# InterfaceUtil.net
KiCad netlist of a schematic drawn in Altium Designer
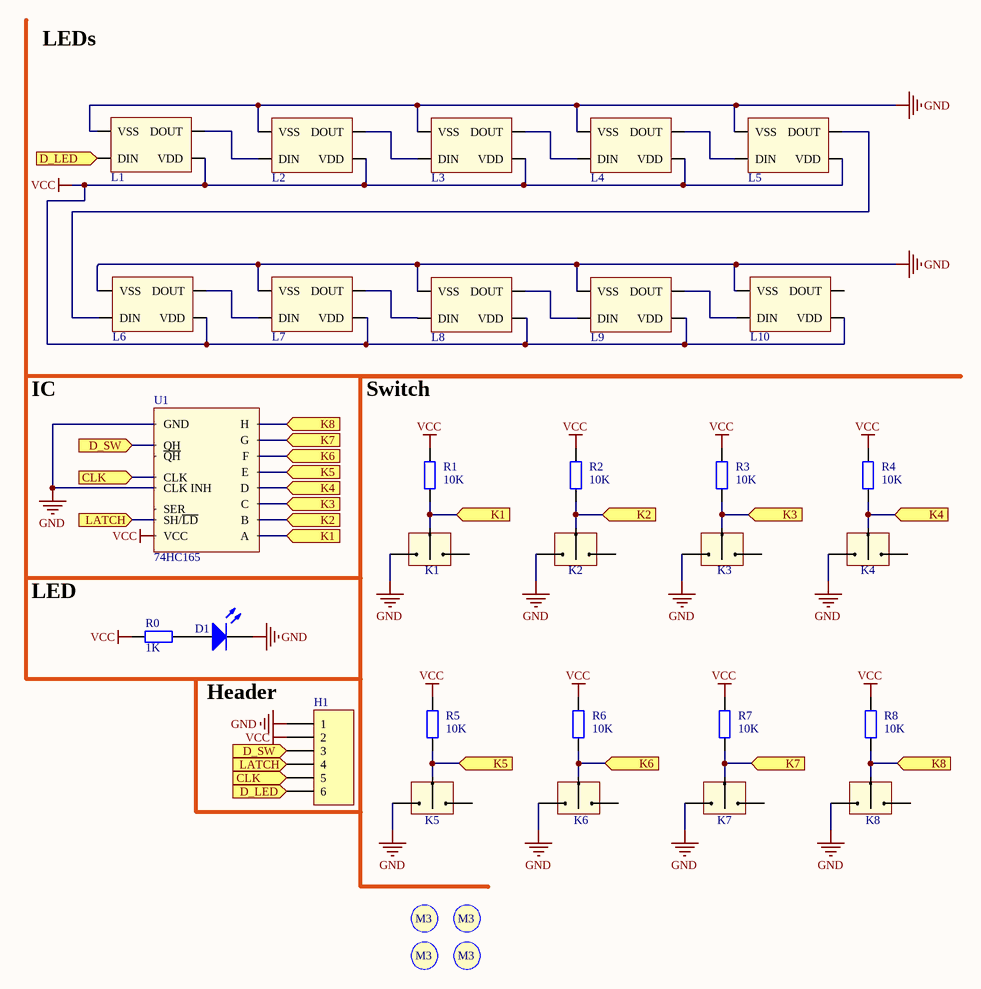
[diagram p0: InterfaceUtil.SchDoc]

(export (version "E")
  (design (tool "Eeschema 10.0.6"))
  (components
    (comp (ref "D1")
      (value "LED2")
      (footprint "3.2X1.6X1.1")
      (description "Typical RED, GREEN, YELLOW, AMBER GaAs LED")
      (fields (field (name "PUBLISHER") "Altium Limited"))
      (libsource (lib "Miscellaneous Devices") (part "LED2"))
    )
    (comp (ref "H1")
      (value "Header 6")
      (footprint "Robot_2019:MOLEX SPOX 6X1H")
      (description "Header, 6-Pin")
      (fields (field (name "PUBLISHER") "Altium Limited"))
      (libsource (lib "Miscellaneous Connectors") (part "Header 6"))
    )
    (comp (ref "K1")
      (value "Switch")
      (footprint "robot:SWITCH")
      (description "3 pos switch, 09.03290.01")
      (libsource (lib "Robot_2019") (part "Switch"))
    )
    (comp (ref "K2")
      (value "Switch")
      (footprint "robot:SWITCH")
      (description "3 pos switch, 09.03290.01")
      (libsource (lib "Robot_2019") (part "Switch"))
    )
    (comp (ref "K3")
      (value "Switch")
      (footprint "robot:SWITCH")
      (description "3 pos switch, 09.03290.01")
      (libsource (lib "Robot_2019") (part "Switch"))
    )
    (comp (ref "K4")
      (value "Switch")
      (footprint "robot:SWITCH")
      (description "3 pos switch, 09.03290.01")
      (libsource (lib "Robot_2019") (part "Switch"))
    )
    (comp (ref "K5")
      (value "Switch")
      (footprint "Robot_2019:SWITCH")
      (description "3 pos switch, 09.03290.01")
      (libsource (lib "Robot_2019") (part "Switch"))
    )
    (comp (ref "K6")
      (value "Switch")
      (footprint "robot:SWITCH")
      (description "3 pos switch, 09.03290.01")
      (libsource (lib "Robot_2019") (part "Switch"))
    )
    (comp (ref "K7")
      (value "Switch")
      (footprint "robot:SWITCH")
      (description "3 pos switch, 09.03290.01")
      (libsource (lib "Robot_2019") (part "Switch"))
    )
    (comp (ref "K8")
      (value "Switch")
      (footprint "robot:SWITCH")
      (description "3 pos switch, 09.03290.01")
      (libsource (lib "Robot_2019") (part "Switch"))
    )
    (comp (ref "L1")
      (value "NeoPixel")
      (footprint "robot:Neopixel")
      (libsource (lib "robot") (part "NeoPixel"))
    )
    (comp (ref "L2")
      (value "NeoPixel")
      (footprint "robot:Neopixel")
      (libsource (lib "robot") (part "NeoPixel"))
    )
    (comp (ref "L3")
      (value "NeoPixel")
      (footprint "robot:Neopixel")
      (libsource (lib "robot") (part "NeoPixel"))
    )
    (comp (ref "L4")
      (value "NeoPixel")
      (footprint "robot:Neopixel")
      (libsource (lib "robot") (part "NeoPixel"))
    )
    (comp (ref "L5")
      (value "NeoPixel")
      (footprint "robot:Neopixel")
      (libsource (lib "robot") (part "NeoPixel"))
    )
    (comp (ref "L6")
      (value "NeoPixel")
      (footprint "robot:Neopixel")
      (libsource (lib "robot") (part "NeoPixel"))
    )
    (comp (ref "L7")
      (value "NeoPixel")
      (footprint "robot:Neopixel")
      (libsource (lib "robot") (part "NeoPixel"))
    )
    (comp (ref "L8")
      (value "NeoPixel")
      (footprint "robot:Neopixel")
      (libsource (lib "robot") (part "NeoPixel"))
    )
    (comp (ref "L9")
      (value "NeoPixel")
      (footprint "robot:Neopixel")
      (libsource (lib "robot") (part "NeoPixel"))
    )
    (comp (ref "L10")
      (value "NeoPixel")
      (footprint "robot:Neopixel")
      (libsource (lib "robot") (part "NeoPixel"))
    )
    (comp (ref "R0")
      (value "1K")
      (footprint "3.2X1.6X1.1")
      (description "Resistor")
      (fields (field (name "Comment") "Res2") (field (name "PUBLISHER") "Altium Limited"))
      (libsource (lib "") (part "Res2_1"))
    )
    (comp (ref "R1")
      (value "10K")
      (footprint "3.2X1.6X1.1")
      (description "Resistor")
      (fields (field (name "Comment") "Res2") (field (name "PUBLISHER") "Altium Limited"))
      (libsource (lib "Miscellaneous Devices") (part "Res2"))
    )
    (comp (ref "R2")
      (value "10K")
      (footprint "3.2X1.6X1.1")
      (description "Resistor")
      (fields (field (name "Comment") "Res2") (field (name "PUBLISHER") "Altium Limited"))
      (libsource (lib "Miscellaneous Devices") (part "Res2"))
    )
    (comp (ref "R3")
      (value "10K")
      (footprint "3.2X1.6X1.1")
      (description "Resistor")
      (fields (field (name "Comment") "Res2") (field (name "PUBLISHER") "Altium Limited"))
      (libsource (lib "Miscellaneous Devices") (part "Res2"))
    )
    (comp (ref "R4")
      (value "10K")
      (footprint "3.2X1.6X1.1")
      (description "Resistor")
      (fields (field (name "Comment") "Res2") (field (name "PUBLISHER") "Altium Limited"))
      (libsource (lib "Miscellaneous Devices") (part "Res2"))
    )
    (comp (ref "R5")
      (value "10K")
      (footprint "3.2X1.6X1.1")
      (description "Resistor")
      (fields (field (name "Comment") "Res2") (field (name "PUBLISHER") "Altium Limited"))
      (libsource (lib "Miscellaneous Devices") (part "Res2"))
    )
    (comp (ref "R6")
      (value "10K")
      (footprint "3.2X1.6X1.1")
      (description "Resistor")
      (fields (field (name "Comment") "Res2") (field (name "PUBLISHER") "Altium Limited"))
      (libsource (lib "Miscellaneous Devices") (part "Res2"))
    )
    (comp (ref "R7")
      (value "10K")
      (footprint "3.2X1.6X1.1")
      (description "Resistor")
      (fields (field (name "Comment") "Res2") (field (name "PUBLISHER") "Altium Limited"))
      (libsource (lib "Miscellaneous Devices") (part "Res2"))
    )
    (comp (ref "R8")
      (value "10K")
      (footprint "3.2X1.6X1.1")
      (description "Resistor")
      (fields (field (name "Comment") "Res2") (field (name "PUBLISHER") "Altium Limited"))
      (libsource (lib "Miscellaneous Devices") (part "Res2"))
    )
    (comp (ref "S1")
      (value "Screw M3")
      (footprint "Robot_2019:Screw M3")
      (libsource (lib "Robot_2019") (part "Screw M3"))
    )
    (comp (ref "S2")
      (value "Screw M3")
      (footprint "Robot_2019:Screw M3")
      (libsource (lib "Robot_2019") (part "Screw M3"))
    )
    (comp (ref "S3")
      (value "Screw M3")
      (footprint "Robot_2019:Screw M3")
      (libsource (lib "Robot_2019") (part "Screw M3"))
    )
    (comp (ref "S4")
      (value "Screw M3")
      (footprint "Robot_2019:Screw M3")
      (libsource (lib "Robot_2019") (part "Screw M3"))
    )
    (comp (ref "U1")
      (value "74HC165")
      (footprint "Robot_2019:16 pins SOIC, TI")
      (description "8 bits Shift Register")
      (libsource (lib "Robot_2019") (part "SN74HC165"))
    )
  )
  (nets
    (net (code "1") (name "/CLK") (class "Default")
      (node (ref "H1") (pin "5") (pinfunction "5_5") (pintype "passive"))
      (node (ref "U1") (pin "2") (pinfunction "CLK_2") (pintype "passive"))
    )
    (net (code "2") (name "/D_LED") (class "Default")
      (node (ref "H1") (pin "6") (pinfunction "6_6") (pintype "passive"))
      (node (ref "L1") (pin "2") (pinfunction "DIN_2") (pintype "passive"))
    )
    (net (code "3") (name "/D_SW") (class "Default")
      (node (ref "H1") (pin "3") (pinfunction "3_3") (pintype "passive"))
      (node (ref "U1") (pin "9") (pinfunction "QH_9") (pintype "passive"))
    )
    (net (code "4") (name "/K1") (class "Default")
      (node (ref "K1") (pin "1") (pinfunction "M_1") (pintype "passive"))
      (node (ref "R1") (pin "1") (pinfunction "1_1") (pintype "passive"))
      (node (ref "U1") (pin "11") (pinfunction "A_11") (pintype "passive"))
    )
    (net (code "5") (name "/K2") (class "Default")
      (node (ref "K2") (pin "1") (pinfunction "M_1") (pintype "passive"))
      (node (ref "R2") (pin "1") (pinfunction "1_1") (pintype "passive"))
      (node (ref "U1") (pin "12") (pinfunction "B_12") (pintype "passive"))
    )
    (net (code "6") (name "/K3") (class "Default")
      (node (ref "K3") (pin "1") (pinfunction "M_1") (pintype "passive"))
      (node (ref "R3") (pin "1") (pinfunction "1_1") (pintype "passive"))
      (node (ref "U1") (pin "13") (pinfunction "C_13") (pintype "passive"))
    )
    (net (code "7") (name "/K4") (class "Default")
      (node (ref "K4") (pin "1") (pinfunction "M_1") (pintype "passive"))
      (node (ref "R4") (pin "1") (pinfunction "1_1") (pintype "passive"))
      (node (ref "U1") (pin "14") (pinfunction "D_14") (pintype "passive"))
    )
    (net (code "8") (name "/K5") (class "Default")
      (node (ref "K5") (pin "1") (pinfunction "M_1") (pintype "passive"))
      (node (ref "R5") (pin "1") (pinfunction "1_1") (pintype "passive"))
      (node (ref "U1") (pin "3") (pinfunction "E_3") (pintype "passive"))
    )
    (net (code "9") (name "/K6") (class "Default")
      (node (ref "K6") (pin "1") (pinfunction "M_1") (pintype "passive"))
      (node (ref "R6") (pin "1") (pinfunction "1_1") (pintype "passive"))
      (node (ref "U1") (pin "4") (pinfunction "F_4") (pintype "passive"))
    )
    (net (code "10") (name "/K7") (class "Default")
      (node (ref "K7") (pin "1") (pinfunction "M_1") (pintype "passive"))
      (node (ref "R7") (pin "1") (pinfunction "1_1") (pintype "passive"))
      (node (ref "U1") (pin "5") (pinfunction "G_5") (pintype "passive"))
    )
    (net (code "11") (name "/K8") (class "Default")
      (node (ref "K8") (pin "1") (pinfunction "M_1") (pintype "passive"))
      (node (ref "R8") (pin "1") (pinfunction "1_1") (pintype "passive"))
      (node (ref "U1") (pin "6") (pinfunction "H_6") (pintype "passive"))
    )
    (net (code "12") (name "/LATCH") (class "Default")
      (node (ref "H1") (pin "4") (pinfunction "4_4") (pintype "passive"))
      (node (ref "U1") (pin "1") (pinfunction "SH/~{LD}_1") (pintype "passive"))
    )
    (net (code "13") (name "GND") (class "Default")
      (node (ref "D1") (pin "2") (pinfunction "K_2") (pintype "passive"))
      (node (ref "H1") (pin "1") (pinfunction "1_1") (pintype "passive"))
      (node (ref "K1") (pin "0") (pinfunction "L_0") (pintype "passive"))
      (node (ref "K2") (pin "0") (pinfunction "L_0") (pintype "passive"))
      (node (ref "K3") (pin "0") (pinfunction "L_0") (pintype "passive"))
      (node (ref "K4") (pin "0") (pinfunction "L_0") (pintype "passive"))
      (node (ref "K5") (pin "0") (pinfunction "L_0") (pintype "passive"))
      (node (ref "K6") (pin "0") (pinfunction "L_0") (pintype "passive"))
      (node (ref "K7") (pin "0") (pinfunction "L_0") (pintype "passive"))
      (node (ref "K8") (pin "0") (pinfunction "L_0") (pintype "passive"))
      (node (ref "L1") (pin "1") (pinfunction "VSS_1") (pintype "passive"))
      (node (ref "L10") (pin "1") (pinfunction "VSS_1") (pintype "passive"))
      (node (ref "L2") (pin "1") (pinfunction "VSS_1") (pintype "passive"))
      (node (ref "L3") (pin "1") (pinfunction "VSS_1") (pintype "passive"))
      (node (ref "L4") (pin "1") (pinfunction "VSS_1") (pintype "passive"))
      (node (ref "L5") (pin "1") (pinfunction "VSS_1") (pintype "passive"))
      (node (ref "L6") (pin "1") (pinfunction "VSS_1") (pintype "passive"))
      (node (ref "L7") (pin "1") (pinfunction "VSS_1") (pintype "passive"))
      (node (ref "L8") (pin "1") (pinfunction "VSS_1") (pintype "passive"))
      (node (ref "L9") (pin "1") (pinfunction "VSS_1") (pintype "passive"))
      (node (ref "U1") (pin "15") (pinfunction "CLK_INH_15") (pintype "passive"))
      (node (ref "U1") (pin "8") (pinfunction "GND_8") (pintype "passive"))
    )
    (net (code "14") (name "Net-(D1-A)") (class "Default")
      (node (ref "D1") (pin "1") (pinfunction "A_1") (pintype "passive"))
      (node (ref "R0") (pin "2") (pinfunction "2_2") (pintype "passive"))
    )
    (net (code "15") (name "Net-(L1-DOUT)") (class "Default")
      (node (ref "L1") (pin "4") (pinfunction "DOUT_4") (pintype "passive"))
      (node (ref "L2") (pin "2") (pinfunction "DIN_2") (pintype "passive"))
    )
    (net (code "16") (name "Net-(L2-DOUT)") (class "Default")
      (node (ref "L2") (pin "4") (pinfunction "DOUT_4") (pintype "passive"))
      (node (ref "L3") (pin "2") (pinfunction "DIN_2") (pintype "passive"))
    )
    (net (code "17") (name "Net-(L3-DOUT)") (class "Default")
      (node (ref "L3") (pin "4") (pinfunction "DOUT_4") (pintype "passive"))
      (node (ref "L4") (pin "2") (pinfunction "DIN_2") (pintype "passive"))
    )
    (net (code "18") (name "Net-(L4-DOUT)") (class "Default")
      (node (ref "L4") (pin "4") (pinfunction "DOUT_4") (pintype "passive"))
      (node (ref "L5") (pin "2") (pinfunction "DIN_2") (pintype "passive"))
    )
    (net (code "19") (name "Net-(L5-DOUT)") (class "Default")
      (node (ref "L5") (pin "4") (pinfunction "DOUT_4") (pintype "passive"))
      (node (ref "L6") (pin "2") (pinfunction "DIN_2") (pintype "passive"))
    )
    (net (code "20") (name "Net-(L6-DOUT)") (class "Default")
      (node (ref "L6") (pin "4") (pinfunction "DOUT_4") (pintype "passive"))
      (node (ref "L7") (pin "2") (pinfunction "DIN_2") (pintype "passive"))
    )
    (net (code "21") (name "Net-(L7-DOUT)") (class "Default")
      (node (ref "L7") (pin "4") (pinfunction "DOUT_4") (pintype "passive"))
      (node (ref "L8") (pin "2") (pinfunction "DIN_2") (pintype "passive"))
    )
    (net (code "22") (name "Net-(L8-DOUT)") (class "Default")
      (node (ref "L8") (pin "4") (pinfunction "DOUT_4") (pintype "passive"))
      (node (ref "L9") (pin "2") (pinfunction "DIN_2") (pintype "passive"))
    )
    (net (code "23") (name "Net-(L10-DIN)") (class "Default")
      (node (ref "L10") (pin "2") (pinfunction "DIN_2") (pintype "passive"))
      (node (ref "L9") (pin "4") (pinfunction "DOUT_4") (pintype "passive"))
    )
    (net (code "24") (name "VCC") (class "Default")
      (node (ref "H1") (pin "2") (pinfunction "2_2") (pintype "passive"))
      (node (ref "L1") (pin "3") (pinfunction "VDD_3") (pintype "passive"))
      (node (ref "L10") (pin "3") (pinfunction "VDD_3") (pintype "passive"))
      (node (ref "L2") (pin "3") (pinfunction "VDD_3") (pintype "passive"))
      (node (ref "L3") (pin "3") (pinfunction "VDD_3") (pintype "passive"))
      (node (ref "L4") (pin "3") (pinfunction "VDD_3") (pintype "passive"))
      (node (ref "L5") (pin "3") (pinfunction "VDD_3") (pintype "passive"))
      (node (ref "L6") (pin "3") (pinfunction "VDD_3") (pintype "passive"))
      (node (ref "L7") (pin "3") (pinfunction "VDD_3") (pintype "passive"))
      (node (ref "L8") (pin "3") (pinfunction "VDD_3") (pintype "passive"))
      (node (ref "L9") (pin "3") (pinfunction "VDD_3") (pintype "passive"))
      (node (ref "R0") (pin "1") (pinfunction "1_1") (pintype "passive"))
      (node (ref "R1") (pin "2") (pinfunction "2_2") (pintype "passive"))
      (node (ref "R2") (pin "2") (pinfunction "2_2") (pintype "passive"))
      (node (ref "R3") (pin "2") (pinfunction "2_2") (pintype "passive"))
      (node (ref "R4") (pin "2") (pinfunction "2_2") (pintype "passive"))
      (node (ref "R5") (pin "2") (pinfunction "2_2") (pintype "passive"))
      (node (ref "R6") (pin "2") (pinfunction "2_2") (pintype "passive"))
      (node (ref "R7") (pin "2") (pinfunction "2_2") (pintype "passive"))
      (node (ref "R8") (pin "2") (pinfunction "2_2") (pintype "passive"))
      (node (ref "U1") (pin "16") (pinfunction "VCC_16") (pintype "passive"))
    )
    (net (code "25") (name "unconnected-(K1-R-Pad2)") (class "Default")
      (node (ref "K1") (pin "2") (pinfunction "R_2") (pintype "passive"))
    )
    (net (code "26") (name "unconnected-(K2-R-Pad2)") (class "Default")
      (node (ref "K2") (pin "2") (pinfunction "R_2") (pintype "passive"))
    )
    (net (code "27") (name "unconnected-(K3-R-Pad2)") (class "Default")
      (node (ref "K3") (pin "2") (pinfunction "R_2") (pintype "passive"))
    )
    (net (code "28") (name "unconnected-(K4-R-Pad2)") (class "Default")
      (node (ref "K4") (pin "2") (pinfunction "R_2") (pintype "passive"))
    )
    (net (code "29") (name "unconnected-(K5-R-Pad2)") (class "Default")
      (node (ref "K5") (pin "2") (pinfunction "R_2") (pintype "passive"))
    )
    (net (code "30") (name "unconnected-(K6-R-Pad2)") (class "Default")
      (node (ref "K6") (pin "2") (pinfunction "R_2") (pintype "passive"))
    )
    (net (code "31") (name "unconnected-(K7-R-Pad2)") (class "Default")
      (node (ref "K7") (pin "2") (pinfunction "R_2") (pintype "passive"))
    )
    (net (code "32") (name "unconnected-(K8-R-Pad2)") (class "Default")
      (node (ref "K8") (pin "2") (pinfunction "R_2") (pintype "passive"))
    )
    (net (code "33") (name "unconnected-(L10-DOUT-Pad4)") (class "Default")
      (node (ref "L10") (pin "4") (pinfunction "DOUT_4") (pintype "passive"))
    )
    (net (code "34") (name "unconnected-(U1-SER-Pad10)") (class "Default")
      (node (ref "U1") (pin "10") (pinfunction "SER_10") (pintype "passive"))
    )
    (net (code "35") (name "unconnected-(U1-~{QH}-Pad7)") (class "Default")
      (node (ref "U1") (pin "7") (pinfunction "~{QH}_7") (pintype "passive"))
    )
  )
)
